# GD_Tcontroller.net
KiCad netlist of a schematic drawn in Altium Designer
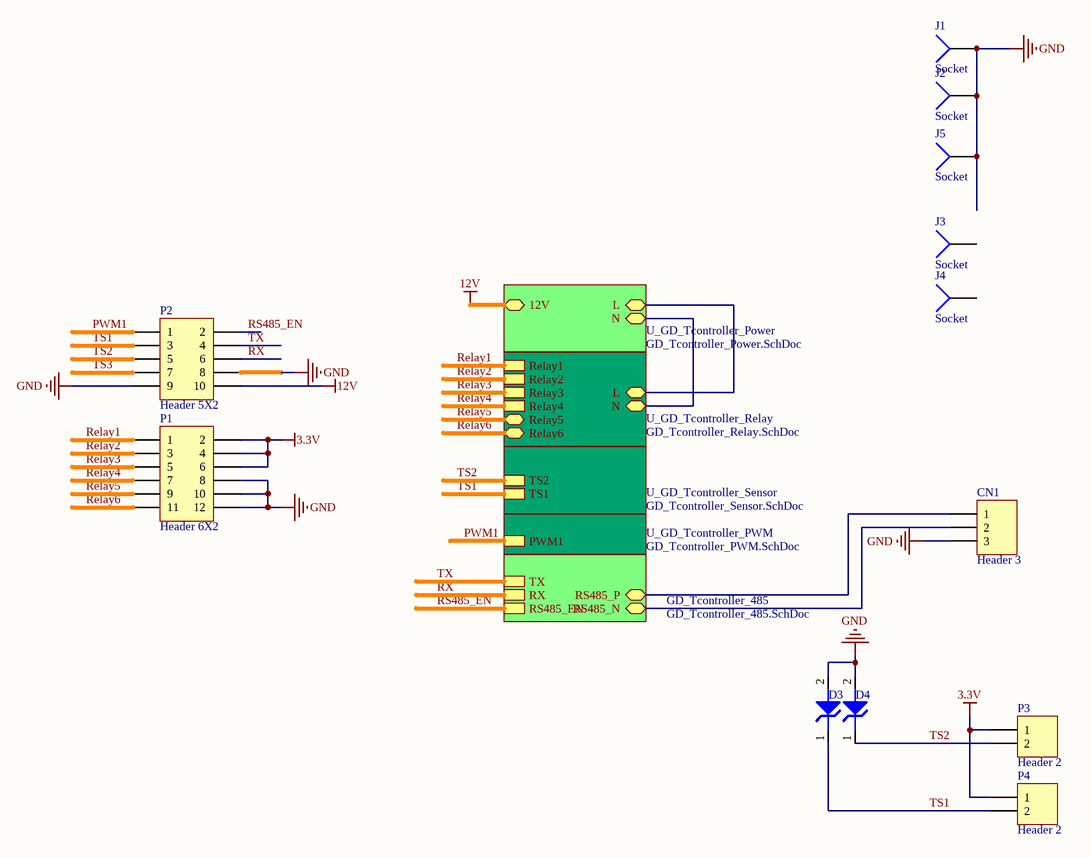
[diagram p0: GD_Tcontroller.SchDoc]

(export (version "E")
  (design (tool "Eeschema 10.0.6"))
  (components
    (comp (ref "CN1")
      (value "Header 3")
      (footprint "HT5.08-3P-H")
      (description "Header, 3-Pin")
      (fields (field (name "PUBLISHER") "Altium Limited"))
      (libsource (lib "Miscellaneous Connectors") (part "Header 3"))
    )
    (comp (ref "D3")
      (value "SMAJ5.0A")
      (footprint "SMA")
      (fields (field (name "MANUFACTURER") "Bourns"))
      (libsource (lib "Enlogic") (part "ZENER"))
    )
    (comp (ref "D4")
      (value "SMAJ5.0A")
      (footprint "SMA")
      (fields (field (name "MANUFACTURER") "Bourns"))
      (libsource (lib "Enlogic") (part "ZENER"))
    )
    (comp (ref "J1")
      (value "Socket")
      (footprint "SCREWFG3_2")
      (fields (field (name "PUBLISHER") "Altium Limited"))
      (libsource (lib "Miscellaneous Connectors") (part "Socket"))
    )
    (comp (ref "J2")
      (value "Socket")
      (footprint "SCREWFG3_2")
      (fields (field (name "PUBLISHER") "Altium Limited"))
      (libsource (lib "Miscellaneous Connectors") (part "Socket"))
    )
    (comp (ref "J3")
      (value "Socket")
      (footprint "SCREWFG3_2")
      (fields (field (name "PUBLISHER") "Altium Limited"))
      (libsource (lib "Miscellaneous Connectors") (part "Socket"))
    )
    (comp (ref "J4")
      (value "Socket")
      (footprint "SCREWFG3_2")
      (fields (field (name "PUBLISHER") "Altium Limited"))
      (libsource (lib "Miscellaneous Connectors") (part "Socket"))
    )
    (comp (ref "J5")
      (value "Socket")
      (footprint "SCREWFG3_2")
      (fields (field (name "PUBLISHER") "Altium Limited"))
      (libsource (lib "Miscellaneous Connectors") (part "Socket"))
    )
    (comp (ref "P1")
      (value "Header 6X2")
      (footprint "DC3-12P")
      (description "Header, 6-Pin, Dual row")
      (fields (field (name "PUBLISHER") "Altium Limited"))
      (libsource (lib "Miscellaneous Connectors") (part "Header 6X2"))
    )
    (comp (ref "P2")
      (value "Header 5X2")
      (footprint "DC3-10P")
      (description "Header, 5-Pin, Dual row")
      (fields (field (name "PUBLISHER") "Altium Limited"))
      (libsource (lib "Miscellaneous Connectors") (part "Header 5X2"))
    )
    (comp (ref "P3")
      (value "Header 2")
      (footprint "PH2.0-2P-H")
      (description "Header, 2-Pin")
      (fields (field (name "PUBLISHER") "Altium Limited"))
      (libsource (lib "Miscellaneous Connectors") (part "Header 2"))
    )
    (comp (ref "P4")
      (value "Header 2")
      (footprint "PH2.0-2P-H")
      (description "Header, 2-Pin")
      (fields (field (name "PUBLISHER") "Altium Limited"))
      (libsource (lib "Miscellaneous Connectors") (part "Header 2"))
    )
  )
  (nets
    (net (code "3") (name "/PWM1") (class "Default")
      (node (ref "P2") (pin "1") (pinfunction "1_1") (pintype "passive"))
    )
    (net (code "4") (name "/RS485_EN") (class "Default")
      (node (ref "P2") (pin "2") (pinfunction "2_2") (pintype "passive"))
    )
    (net (code "5") (name "/RS485_N") (class "Default")
      (node (ref "CN1") (pin "2") (pinfunction "2_2") (pintype "passive"))
    )
    (net (code "6") (name "/RS485_P") (class "Default")
      (node (ref "CN1") (pin "1") (pinfunction "1_1") (pintype "passive"))
    )
    (net (code "7") (name "/RX") (class "Default")
      (node (ref "P2") (pin "6") (pinfunction "6_6") (pintype "passive"))
    )
    (net (code "8") (name "/Relay1") (class "Default")
      (node (ref "P1") (pin "1") (pinfunction "1_1") (pintype "passive"))
    )
    (net (code "9") (name "/Relay2") (class "Default")
      (node (ref "P1") (pin "3") (pinfunction "3_3") (pintype "passive"))
    )
    (net (code "10") (name "/Relay3") (class "Default")
      (node (ref "P1") (pin "5") (pinfunction "5_5") (pintype "passive"))
    )
    (net (code "11") (name "/Relay4") (class "Default")
      (node (ref "P1") (pin "7") (pinfunction "7_7") (pintype "passive"))
    )
    (net (code "12") (name "/Relay5") (class "Default")
      (node (ref "P1") (pin "9") (pinfunction "9_9") (pintype "passive"))
    )
    (net (code "13") (name "/Relay6") (class "Default")
      (node (ref "P1") (pin "11") (pinfunction "11_11") (pintype "passive"))
    )
    (net (code "14") (name "/TS1") (class "Default")
      (node (ref "D3") (pin "1") (pintype "passive"))
      (node (ref "P2") (pin "3") (pinfunction "3_3") (pintype "passive"))
      (node (ref "P4") (pin "2") (pinfunction "2_2") (pintype "passive"))
    )
    (net (code "15") (name "/TS2") (class "Default")
      (node (ref "D4") (pin "1") (pintype "passive"))
      (node (ref "P2") (pin "5") (pinfunction "5_5") (pintype "passive"))
      (node (ref "P3") (pin "2") (pinfunction "2_2") (pintype "passive"))
    )
    (net (code "16") (name "/TS3") (class "Default")
      (node (ref "P2") (pin "7") (pinfunction "7_7") (pintype "passive"))
    )
    (net (code "17") (name "/TX") (class "Default")
      (node (ref "P2") (pin "4") (pinfunction "4_4") (pintype "passive"))
    )
    (net (code "18") (name "3.3V") (class "Default")
      (node (ref "P1") (pin "2") (pinfunction "2_2") (pintype "passive"))
      (node (ref "P1") (pin "4") (pinfunction "4_4") (pintype "passive"))
      (node (ref "P1") (pin "6") (pinfunction "6_6") (pintype "passive"))
      (node (ref "P3") (pin "1") (pinfunction "1_1") (pintype "passive"))
      (node (ref "P4") (pin "1") (pinfunction "1_1") (pintype "passive"))
    )
    (net (code "19") (name "12V") (class "Default")
      (node (ref "P2") (pin "10") (pinfunction "10_10") (pintype "passive"))
    )
    (net (code "20") (name "GND") (class "Default")
      (node (ref "CN1") (pin "3") (pinfunction "3_3") (pintype "passive"))
      (node (ref "D3") (pin "2") (pintype "passive"))
      (node (ref "D4") (pin "2") (pintype "passive"))
      (node (ref "J1") (pin "1") (pinfunction "1_1") (pintype "passive"))
      (node (ref "J2") (pin "1") (pinfunction "1_1") (pintype "passive"))
      (node (ref "J5") (pin "1") (pinfunction "1_1") (pintype "passive"))
      (node (ref "P1") (pin "10") (pinfunction "10_10") (pintype "passive"))
      (node (ref "P1") (pin "12") (pinfunction "12_12") (pintype "passive"))
      (node (ref "P1") (pin "8") (pinfunction "8_8") (pintype "passive"))
      (node (ref "P2") (pin "8") (pinfunction "8_8") (pintype "passive"))
      (node (ref "P2") (pin "9") (pinfunction "9_9") (pintype "passive"))
    )
    (net (code "21") (name "unconnected-(J3-Pad1)") (class "Default")
      (node (ref "J3") (pin "1") (pinfunction "1_1") (pintype "passive"))
    )
    (net (code "22") (name "unconnected-(J4-Pad1)") (class "Default")
      (node (ref "J4") (pin "1") (pinfunction "1_1") (pintype "passive"))
    )
  )
)
